# BradLightFlash_rev1.net
KiCad netlist of a schematic drawn in EAGLE
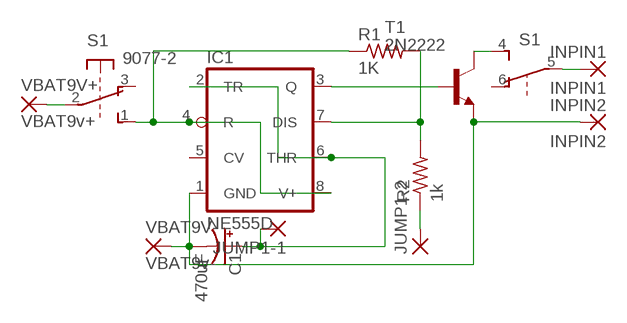
[diagram p0: schematic, sheet 1]

(export (version "E")
  (design (tool "Eeschema 10.0.6"))
  (components
    (comp (ref "C1")
      (value "470uF")
      (footprint "eagle-import:E2,5-6")
      (libsource (lib "eagle-import") (part "CPOL-USE2.5-6"))
    )
    (comp (ref "IC1")
      (value "NE555D")
      (footprint "eagle-import:SO08")
      (libsource (lib "eagle-import") (part "555DNE"))
    )
    (comp (ref "INPIN1")
      (value "INPIN1")
      (footprint "eagle-import:2,54_1,1")
      (libsource (lib "eagle-import") (part "2,54/1,1"))
    )
    (comp (ref "INPIN2")
      (value "INPIN2")
      (footprint "eagle-import:2,54_1,1")
      (libsource (lib "eagle-import") (part "2,54/1,1"))
    )
    (comp (ref "JUMP1-1")
      (value "2,54/1,0")
      (footprint "eagle-import:2,54_1,0")
      (libsource (lib "eagle-import") (part "2,54/1,0"))
    )
    (comp (ref "JUMP1-2")
      (value "2,54/1,0")
      (footprint "eagle-import:2,54_1,0")
      (libsource (lib "eagle-import") (part "2,54/1,0"))
    )
    (comp (ref "R1")
      (value "1K")
      (footprint "eagle-import:0309V")
      (libsource (lib "eagle-import") (part "R-US_0309/V"))
    )
    (comp (ref "R2")
      (value "1k")
      (footprint "eagle-import:0309V")
      (libsource (lib "eagle-import") (part "R-US_0309/V"))
    )
    (comp (ref "S1")
      (value "9077-2")
      (footprint "eagle-import:9077-2")
      (libsource (lib "eagle-import") (part "9077-2"))
    )
    (comp (ref "T1")
      (value "2N2222")
      (footprint "eagle-import:TO92-EBC-OVAL")
      (libsource (lib "eagle-import") (part "2N2222"))
    )
    (comp (ref "VBAT9V+")
      (value "VBAT9v+")
      (footprint "eagle-import:2,54_1,1")
      (libsource (lib "eagle-import") (part "2,54/1,1"))
    )
    (comp (ref "VBAT9V-")
      (value "VBAT9v-")
      (footprint "eagle-import:2,54_1,1")
      (libsource (lib "eagle-import") (part "2,54/1,1"))
    )
  )
  (nets
    (net (code "1") (name "Net-(IC1-DIS)") (class "Default")
      (node (ref "IC1") (pin "7") (pinfunction "DIS_7") (pintype "input"))
      (node (ref "R1") (pin "2") (pinfunction "2_2") (pintype "passive"))
      (node (ref "R2") (pin "2") (pinfunction "2_2") (pintype "passive"))
    )
    (net (code "2") (name "Net-(IC1-GND)") (class "Default")
      (node (ref "C1") (pin "-") (pinfunction "-_-") (pintype "passive"))
      (node (ref "IC1") (pin "1") (pinfunction "GND_1") (pintype "power_in"))
      (node (ref "INPIN2") (pin "1") (pinfunction "P_1") (pintype "passive"))
      (node (ref "T1") (pin "E") (pinfunction "E_E") (pintype "passive"))
      (node (ref "VBAT9V-") (pin "1") (pinfunction "P_1") (pintype "passive"))
    )
    (net (code "3") (name "Net-(IC1-Q)") (class "Default")
      (node (ref "IC1") (pin "3") (pinfunction "Q_3") (pintype "output"))
      (node (ref "T1") (pin "B") (pinfunction "B_B") (pintype "passive"))
    )
    (net (code "4") (name "Net-(IC1-R)") (class "Default")
      (node (ref "IC1") (pin "4") (pinfunction "R_4") (pintype "input"))
      (node (ref "IC1") (pin "8") (pinfunction "V+_8") (pintype "power_in"))
      (node (ref "R1") (pin "1") (pinfunction "1_1") (pintype "passive"))
      (node (ref "S1") (pin "1") (pinfunction "S_1") (pintype "passive"))
    )
    (net (code "5") (name "Net-(IC1-THR)") (class "Default")
      (node (ref "C1") (pin "+") (pinfunction "+_+") (pintype "passive"))
      (node (ref "IC1") (pin "2") (pinfunction "TR_2") (pintype "input"))
      (node (ref "IC1") (pin "6") (pinfunction "THR_6") (pintype "input"))
      (node (ref "JUMP1-1") (pin "1") (pinfunction "P_1") (pintype "passive"))
    )
    (net (code "6") (name "Net-(INPIN1-P)") (class "Default")
      (node (ref "INPIN1") (pin "1") (pinfunction "P_1") (pintype "passive"))
      (node (ref "S1") (pin "5") (pinfunction "P_5") (pintype "passive"))
    )
    (net (code "7") (name "Net-(JUMP1-2-P)") (class "Default")
      (node (ref "JUMP1-2") (pin "1") (pinfunction "P_1") (pintype "passive"))
      (node (ref "R2") (pin "1") (pinfunction "1_1") (pintype "passive"))
    )
    (net (code "8") (name "Net-(S1A-P)") (class "Default")
      (node (ref "S1") (pin "2") (pinfunction "P_2") (pintype "passive"))
      (node (ref "VBAT9V+") (pin "1") (pinfunction "P_1") (pintype "passive"))
    )
    (net (code "9") (name "Net-(S1B-S)") (class "Default")
      (node (ref "S1") (pin "4") (pinfunction "S_4") (pintype "passive"))
      (node (ref "T1") (pin "C") (pinfunction "C_C") (pintype "passive"))
    )
    (net (code "10") (name "unconnected-(IC1-CV-Pad5)") (class "Default")
      (node (ref "IC1") (pin "5") (pinfunction "CV_5") (pintype "input"))
    )
    (net (code "11") (name "unconnected-(S1A-O-Pad3)") (class "Default")
      (node (ref "S1") (pin "3") (pinfunction "O_3") (pintype "passive"))
    )
    (net (code "12") (name "unconnected-(S1B-O-Pad6)") (class "Default")
      (node (ref "S1") (pin "6") (pinfunction "O_6") (pintype "passive"))
    )
  )
)
